# tiny_control.net
KiCad netlist of a schematic drawn in Altium Designer
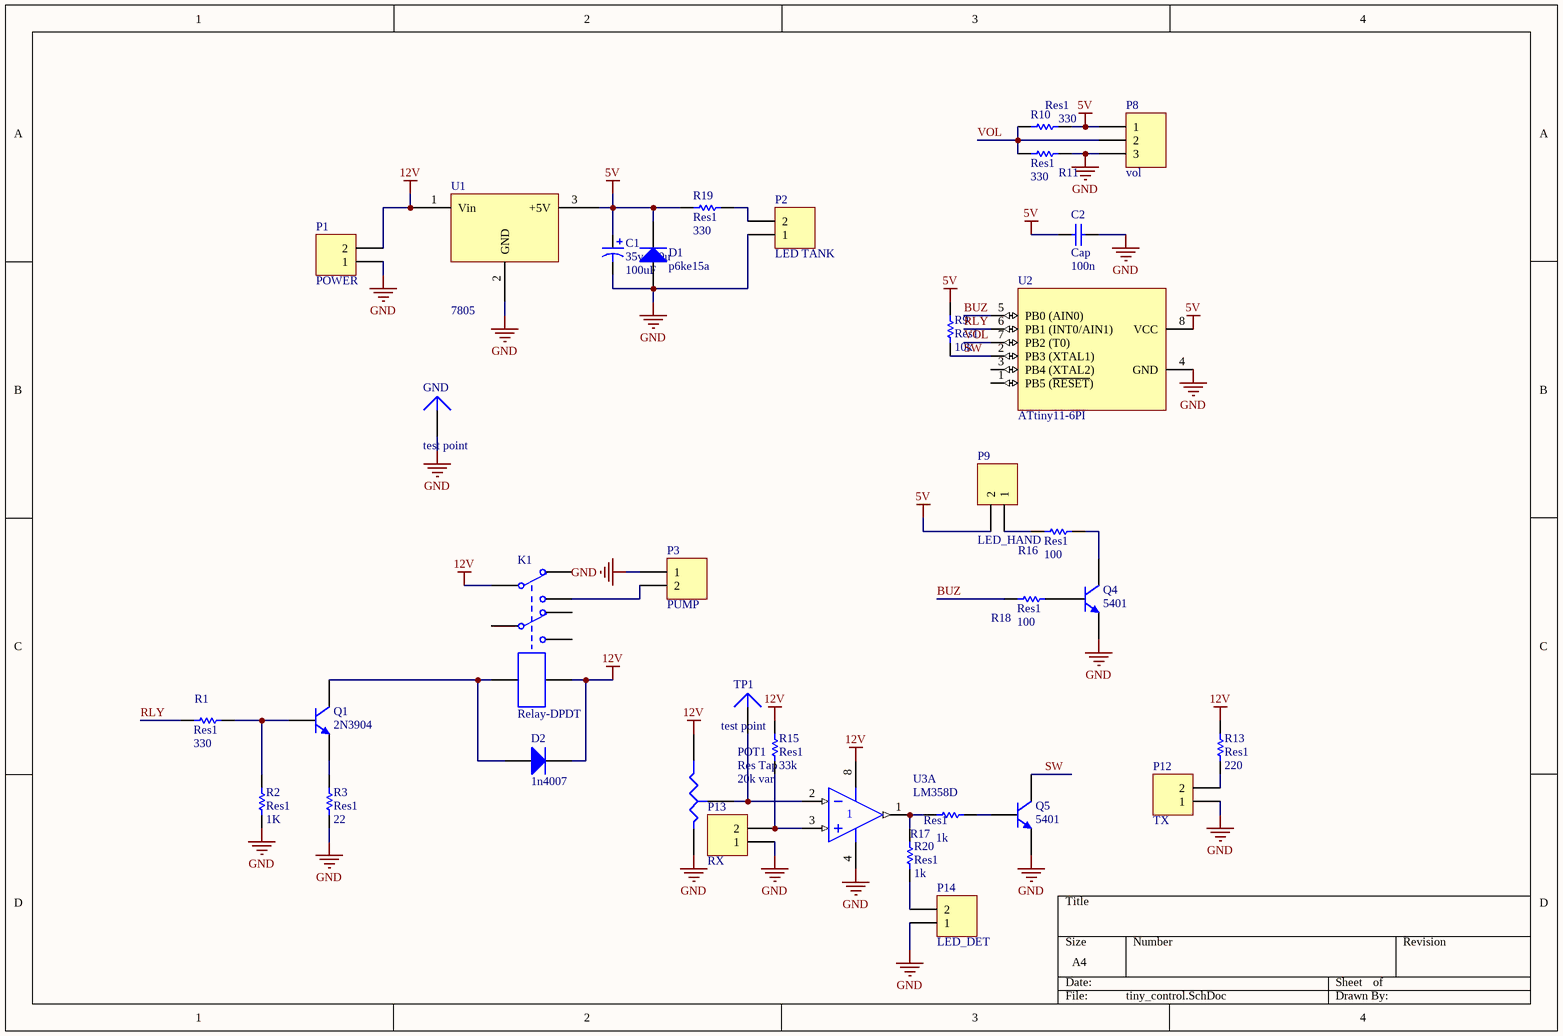
[diagram p0: tiny_control.SchDoc]

(export (version "E")
  (design (tool "Eeschema 10.0.6"))
  (components
    (comp (ref "C1")
      (value "35v 100u")
      (footprint "cap5")
      (description "ELECTROLITE 25V")
      (fields (field (name "ALTIUM_VALUE") "100uF"))
      (libsource (lib "Miscellaneous Devices") (part "Cap Pol1"))
    )
    (comp (ref "C2")
      (value "Cap")
      (footprint "RAD-0.1")
      (description "Capacitor")
      (fields (field (name "ALTIUM_VALUE") "100n") (field (name "PUBLISHER") "Altium Limited"))
      (libsource (lib "Miscellaneous Devices") (part "Cap"))
    )
    (comp (ref "D1")
      (value "p6ke15a")
      (footprint "DIODE-0.4")
      (description "High Conductance Fast Diode")
      (libsource (lib "Miscellaneous Devices") (part "Diode 1N4148"))
    )
    (comp (ref "D2")
      (value "1n4007")
      (footprint "DIO7.1-3.9x1.9")
      (description "High Conductance Fast Diode")
      (libsource (lib "Miscellaneous Devices") (part "Diode 1N4148"))
    )
    (comp (ref "GND")
      (value "test point")
      (footprint "PIN1")
      (description "Plug")
      (fields (field (name "PUBLISHER") "Altium Limited"))
      (libsource (lib "Miscellaneous Connectors") (part "Plug"))
    )
    (comp (ref "K1")
      (value "Relay-DPDT")
      (footprint "My_REL_cochick")
      (description "Dual-Pole Dual-Throw Relay")
      (fields (field (name "PUBLISHER") "Altium Limited"))
      (libsource (lib "Miscellaneous Devices") (part "Relay-DPDT"))
    )
    (comp (ref "P1")
      (value "POWER")
      (footprint "con2_2.54")
      (description "Header, 2-Pin")
      (fields (field (name "PUBLISHER") "Altium Limited"))
      (libsource (lib "Miscellaneous Connectors") (part "Header 2"))
    )
    (comp (ref "P2")
      (value "LED TANK")
      (footprint "con2_2.54")
      (description "Header, 2-Pin")
      (fields (field (name "PUBLISHER") "Altium Limited"))
      (libsource (lib "") (part "Header 2_2"))
    )
    (comp (ref "P3")
      (value "PUMP")
      (footprint "con2_2.54")
      (description "Header, 2-Pin")
      (fields (field (name "PUBLISHER") "Altium Limited"))
      (libsource (lib "") (part "Header 2_1"))
    )
    (comp (ref "P8")
      (value "vol")
      (footprint "con3_2.54")
      (description "Header, 3-Pin")
      (fields (field (name "PUBLISHER") "Altium Limited"))
      (libsource (lib "Miscellaneous Connectors") (part "Header 3"))
    )
    (comp (ref "P9")
      (value "LED_HAND")
      (footprint "con2_2.54")
      (description "Header, 2-Pin")
      (fields (field (name "PUBLISHER") "Altium Limited"))
      (libsource (lib "") (part "Header 2_1"))
    )
    (comp (ref "P12")
      (value "TX")
      (footprint "con2_2.54")
      (description "Header, 2-Pin")
      (fields (field (name "PUBLISHER") "Altium Limited"))
      (libsource (lib "Miscellaneous Connectors") (part "Header 2"))
    )
    (comp (ref "P13")
      (value "RX")
      (footprint "con2_2.54")
      (description "Header, 2-Pin")
      (fields (field (name "PUBLISHER") "Altium Limited"))
      (libsource (lib "Miscellaneous Connectors") (part "Header 2"))
    )
    (comp (ref "P14")
      (value "LED_DET")
      (footprint "con2_2.54")
      (description "Header, 2-Pin")
      (fields (field (name "PUBLISHER") "Altium Limited"))
      (libsource (lib "") (part "Header 2_2"))
    )
    (comp (ref "POT1")
      (value "Res Tap")
      (footprint "VR5")
      (description "Tapped Resistor")
      (fields (field (name "ALTIUM_VALUE") "20k var"))
      (libsource (lib "Miscellaneous Devices") (part "Res Tap"))
    )
    (comp (ref "Q1")
      (value "2N3904")
      (footprint "TO-92C")
      (description "NPN General Purpose Amplifier")
      (fields (field (name "PUBLISHER") "Altium Limited"))
      (libsource (lib "Miscellaneous Devices") (part "2N3904"))
    )
    (comp (ref "Q4")
      (value "5401")
      (footprint "TO-92C")
      (description "Transistor")
      (fields (field (name "PUBLISHER") "Altium Limited"))
      (libsource (lib "Motorola Discrete BJT") (part "P2N2222A"))
    )
    (comp (ref "Q5")
      (value "5401")
      (footprint "TO-92C")
      (description "Transistor")
      (fields (field (name "PUBLISHER") "Altium Limited"))
      (libsource (lib "Motorola Discrete BJT") (part "P2N2222A"))
    )
    (comp (ref "R1")
      (value "Res1")
      (footprint "AXIAL-0.3")
      (description "Resistor")
      (fields (field (name "ALTIUM_VALUE") "330") (field (name "PUBLISHER") "Altium Limited"))
      (libsource (lib "Miscellaneous Devices") (part "Res1"))
    )
    (comp (ref "R2")
      (value "Res1")
      (footprint "AXIAL-0.3")
      (description "Resistor")
      (fields (field (name "ALTIUM_VALUE") "1K") (field (name "PUBLISHER") "Altium Limited"))
      (libsource (lib "Miscellaneous Devices") (part "Res1"))
    )
    (comp (ref "R3")
      (value "Res1")
      (footprint "AXIAL-0.3")
      (description "Resistor")
      (fields (field (name "ALTIUM_VALUE") "22") (field (name "PUBLISHER") "Altium Limited"))
      (libsource (lib "Miscellaneous Devices") (part "Res1"))
    )
    (comp (ref "R9")
      (value "Res1")
      (footprint "AXIAL-0.3")
      (description "Resistor")
      (fields (field (name "ALTIUM_VALUE") "10k") (field (name "PUBLISHER") "Altium Limited"))
      (libsource (lib "Miscellaneous Devices") (part "Res1"))
    )
    (comp (ref "R10")
      (value "Res1")
      (footprint "AXIAL-0.3")
      (description "Resistor")
      (fields (field (name "ALTIUM_VALUE") "330") (field (name "PUBLISHER") "Altium Limited"))
      (libsource (lib "Miscellaneous Devices") (part "Res1"))
    )
    (comp (ref "R11")
      (value "Res1")
      (footprint "AXIAL-0.3")
      (description "Resistor")
      (fields (field (name "ALTIUM_VALUE") "330") (field (name "PUBLISHER") "Altium Limited"))
      (libsource (lib "Miscellaneous Devices") (part "Res1"))
    )
    (comp (ref "R13")
      (value "Res1")
      (footprint "AXIAL-0.3")
      (description "Resistor")
      (fields (field (name "ALTIUM_VALUE") "220") (field (name "PUBLISHER") "Altium Limited"))
      (libsource (lib "Miscellaneous Devices") (part "Res1"))
    )
    (comp (ref "R15")
      (value "Res1")
      (footprint "AXIAL-0.3")
      (description "Resistor")
      (fields (field (name "ALTIUM_VALUE") "33k") (field (name "PUBLISHER") "Altium Limited"))
      (libsource (lib "Miscellaneous Devices") (part "Res1"))
    )
    (comp (ref "R16")
      (value "Res1")
      (footprint "AXIAL-0.3")
      (description "Resistor")
      (fields (field (name "ALTIUM_VALUE") "100") (field (name "PUBLISHER") "Altium Limited"))
      (libsource (lib "Miscellaneous Devices") (part "Res1"))
    )
    (comp (ref "R17")
      (value "Res1")
      (footprint "AXIAL-0.3")
      (description "Resistor")
      (fields (field (name "ALTIUM_VALUE") "1k") (field (name "PUBLISHER") "Altium Limited"))
      (libsource (lib "Miscellaneous Devices") (part "Res1"))
    )
    (comp (ref "R18")
      (value "Res1")
      (footprint "AXIAL-0.3")
      (description "Resistor")
      (fields (field (name "ALTIUM_VALUE") "100") (field (name "PUBLISHER") "Altium Limited"))
      (libsource (lib "Miscellaneous Devices") (part "Res1"))
    )
    (comp (ref "R19")
      (value "Res1")
      (footprint "AXIAL-0.3")
      (description "Resistor")
      (fields (field (name "ALTIUM_VALUE") "330") (field (name "PUBLISHER") "Altium Limited"))
      (libsource (lib "Miscellaneous Devices") (part "Res1"))
    )
    (comp (ref "R20")
      (value "Res1")
      (footprint "AXIAL-0.3")
      (description "Resistor")
      (fields (field (name "ALTIUM_VALUE") "1k") (field (name "PUBLISHER") "Altium Limited"))
      (libsource (lib "Miscellaneous Devices") (part "Res1"))
    )
    (comp (ref "TP1")
      (value "test point")
      (footprint "PIN1")
      (description "Plug")
      (fields (field (name "PUBLISHER") "Altium Limited"))
      (libsource (lib "Miscellaneous Connectors") (part "Plug"))
    )
    (comp (ref "U1")
      (value "7805")
      (footprint "TO-220")
      (description "Regulator")
      (libsource (lib "AHO") (part "7805"))
    )
    (comp (ref "U2")
      (value "ATtiny11-6PI")
      (footprint "SOIC-8")
      (description "AVR 1K Byte of Flash Memory")
      (fields (field (name "PUBLISHER") "Altium Limited"))
      (libsource (lib "AHO") (part "ATtiny11-6PI"))
    )
    (comp (ref "U3")
      (value "LM358D")
      (footprint "SOIC-8")
      (description "Dual Low-Power Operational Amplifier")
      (libsource (lib "Motorola Amplifier Operational Amplifier") (part "LM358D"))
    )
  )
  (nets
    (net (code "1") (name "/BUZ") (class "Default")
      (node (ref "R18") (pin "1") (pinfunction "1_1") (pintype "passive"))
      (node (ref "U2") (pin "5") (pinfunction "PB0_(AIN0)_5") (pintype "bidirectional"))
    )
    (net (code "2") (name "/RLY") (class "Default")
      (node (ref "R1") (pin "1") (pinfunction "1_1") (pintype "passive"))
      (node (ref "U2") (pin "6") (pinfunction "PB1_(INT0/AIN1)_6") (pintype "bidirectional"))
    )
    (net (code "3") (name "/SW") (class "Default")
      (node (ref "Q5") (pin "1") (pinfunction "C_1") (pintype "passive"))
      (node (ref "R9") (pin "2") (pinfunction "2_2") (pintype "passive"))
      (node (ref "U2") (pin "2") (pinfunction "PB3_(XTAL1)_2") (pintype "bidirectional"))
    )
    (net (code "4") (name "/VOL") (class "Default")
      (node (ref "P8") (pin "2") (pinfunction "2_2") (pintype "passive"))
      (node (ref "R10") (pin "2") (pinfunction "2_2") (pintype "passive"))
      (node (ref "R11") (pin "2") (pinfunction "2_2") (pintype "passive"))
      (node (ref "U2") (pin "7") (pinfunction "PB2_(T0)_7") (pintype "bidirectional"))
    )
    (net (code "5") (name "5V") (class "Default")
      (node (ref "C1") (pin "1") (pinfunction "1_1") (pintype "passive"))
      (node (ref "C2") (pin "1") (pinfunction "1_1") (pintype "passive"))
      (node (ref "D1") (pin "2") (pinfunction "K_2") (pintype "passive"))
      (node (ref "P8") (pin "1") (pinfunction "1_1") (pintype "passive"))
      (node (ref "P9") (pin "2") (pinfunction "2_2") (pintype "passive"))
      (node (ref "R10") (pin "1") (pinfunction "1_1") (pintype "passive"))
      (node (ref "R19") (pin "2") (pinfunction "2_2") (pintype "passive"))
      (node (ref "R9") (pin "1") (pinfunction "1_1") (pintype "passive"))
      (node (ref "U1") (pin "3") (pinfunction "+5V_3") (pintype "power_in"))
      (node (ref "U2") (pin "8") (pinfunction "VCC_8") (pintype "power_in"))
    )
    (net (code "6") (name "12V") (class "Default")
      (node (ref "D2") (pin "2") (pinfunction "K_2") (pintype "passive"))
      (node (ref "K1") (pin "1") (pinfunction "1_1") (pintype "passive"))
      (node (ref "K1") (pin "8") (pinfunction "8_8") (pintype "passive"))
      (node (ref "P1") (pin "2") (pinfunction "2_2") (pintype "passive"))
      (node (ref "POT1") (pin "3") (pinfunction "3_3") (pintype "passive"))
      (node (ref "R13") (pin "2") (pinfunction "2_2") (pintype "passive"))
      (node (ref "R15") (pin "2") (pinfunction "2_2") (pintype "passive"))
      (node (ref "U1") (pin "1") (pinfunction "Vin_1") (pintype "power_in"))
      (node (ref "U3") (pin "8") (pinfunction "V+_8") (pintype "power_in"))
    )
    (net (code "7") (name "GND") (class "Default")
      (node (ref "C1") (pin "2") (pinfunction "2_2") (pintype "passive"))
      (node (ref "C2") (pin "2") (pinfunction "2_2") (pintype "passive"))
      (node (ref "D1") (pin "1") (pinfunction "A_1") (pintype "passive"))
      (node (ref "GND") (pin "1") (pinfunction "1_1") (pintype "passive"))
      (node (ref "P1") (pin "1") (pinfunction "1_1") (pintype "passive"))
      (node (ref "P12") (pin "1") (pinfunction "1_1") (pintype "passive"))
      (node (ref "P13") (pin "1") (pinfunction "1_1") (pintype "passive"))
      (node (ref "P14") (pin "1") (pinfunction "1_1") (pintype "passive"))
      (node (ref "P2") (pin "1") (pinfunction "1_1") (pintype "passive"))
      (node (ref "P3") (pin "1") (pinfunction "1_1") (pintype "passive"))
      (node (ref "P8") (pin "3") (pinfunction "3_3") (pintype "passive"))
      (node (ref "POT1") (pin "1") (pinfunction "1_1") (pintype "passive"))
      (node (ref "Q4") (pin "3") (pinfunction "E_3") (pintype "passive"))
      (node (ref "Q5") (pin "3") (pinfunction "E_3") (pintype "passive"))
      (node (ref "R11") (pin "1") (pinfunction "1_1") (pintype "passive"))
      (node (ref "R2") (pin "1") (pinfunction "1_1") (pintype "passive"))
      (node (ref "R3") (pin "1") (pinfunction "1_1") (pintype "passive"))
      (node (ref "U1") (pin "2") (pinfunction "GND_2") (pintype "power_in"))
      (node (ref "U2") (pin "4") (pinfunction "GND_4") (pintype "power_in"))
      (node (ref "U3") (pin "4") (pinfunction "V-_4") (pintype "power_in"))
    )
    (net (code "8") (name "Net-(D2-A)") (class "Default")
      (node (ref "D2") (pin "1") (pinfunction "A_1") (pintype "passive"))
      (node (ref "K1") (pin "7") (pinfunction "7_7") (pintype "passive"))
      (node (ref "Q1") (pin "3") (pinfunction "C_3") (pintype "passive"))
    )
    (net (code "9") (name "Net-(K1-Pad3)") (class "Default")
      (node (ref "K1") (pin "3") (pinfunction "3_3") (pintype "passive"))
      (node (ref "P3") (pin "2") (pinfunction "2_2") (pintype "passive"))
    )
    (net (code "10") (name "Net-(P2-Pad2)") (class "Default")
      (node (ref "P2") (pin "2") (pinfunction "2_2") (pintype "passive"))
      (node (ref "R19") (pin "1") (pinfunction "1_1") (pintype "passive"))
    )
    (net (code "11") (name "Net-(P9-Pad1)") (class "Default")
      (node (ref "P9") (pin "1") (pinfunction "1_1") (pintype "passive"))
      (node (ref "R16") (pin "1") (pinfunction "1_1") (pintype "passive"))
    )
    (net (code "12") (name "Net-(P12-Pad2)") (class "Default")
      (node (ref "P12") (pin "2") (pinfunction "2_2") (pintype "passive"))
      (node (ref "R13") (pin "1") (pinfunction "1_1") (pintype "passive"))
    )
    (net (code "13") (name "Net-(P14-Pad2)") (class "Default")
      (node (ref "P14") (pin "2") (pinfunction "2_2") (pintype "passive"))
      (node (ref "R20") (pin "1") (pinfunction "1_1") (pintype "passive"))
    )
    (net (code "14") (name "Net-(Q1-B)") (class "Default")
      (node (ref "Q1") (pin "2") (pinfunction "B_2") (pintype "passive"))
      (node (ref "R1") (pin "2") (pinfunction "2_2") (pintype "passive"))
      (node (ref "R2") (pin "2") (pinfunction "2_2") (pintype "passive"))
    )
    (net (code "15") (name "Net-(Q1-E)") (class "Default")
      (node (ref "Q1") (pin "1") (pinfunction "E_1") (pintype "passive"))
      (node (ref "R3") (pin "2") (pinfunction "2_2") (pintype "passive"))
    )
    (net (code "16") (name "Net-(Q4-B)") (class "Default")
      (node (ref "Q4") (pin "2") (pinfunction "B_2") (pintype "passive"))
      (node (ref "R18") (pin "2") (pinfunction "2_2") (pintype "passive"))
    )
    (net (code "17") (name "Net-(Q4-C)") (class "Default")
      (node (ref "Q4") (pin "1") (pinfunction "C_1") (pintype "passive"))
      (node (ref "R16") (pin "2") (pinfunction "2_2") (pintype "passive"))
    )
    (net (code "18") (name "Net-(Q5-B)") (class "Default")
      (node (ref "Q5") (pin "2") (pinfunction "B_2") (pintype "passive"))
      (node (ref "R17") (pin "2") (pinfunction "2_2") (pintype "passive"))
    )
    (net (code "19") (name "Net-(U3A-IN+)") (class "Default")
      (node (ref "P13") (pin "2") (pinfunction "2_2") (pintype "passive"))
      (node (ref "R15") (pin "1") (pinfunction "1_1") (pintype "passive"))
      (node (ref "U3") (pin "3") (pinfunction "IN+_3") (pintype "input"))
    )
    (net (code "20") (name "Net-(U3A-IN-)") (class "Default")
      (node (ref "POT1") (pin "2") (pinfunction "2_2") (pintype "passive"))
      (node (ref "TP1") (pin "1") (pinfunction "1_1") (pintype "passive"))
      (node (ref "U3") (pin "2") (pinfunction "IN-_2") (pintype "input"))
    )
    (net (code "21") (name "Net-(U3A-OUT)") (class "Default")
      (node (ref "R17") (pin "1") (pinfunction "1_1") (pintype "passive"))
      (node (ref "R20") (pin "2") (pinfunction "2_2") (pintype "passive"))
      (node (ref "U3") (pin "1") (pinfunction "OUT_1") (pintype "output"))
    )
    (net (code "22") (name "unconnected-(K1-Pad2)") (class "Default")
      (node (ref "K1") (pin "2") (pinfunction "2_2") (pintype "passive"))
    )
    (net (code "23") (name "unconnected-(K1-Pad4)") (class "Default")
      (node (ref "K1") (pin "4") (pinfunction "4_4") (pintype "passive"))
    )
    (net (code "24") (name "unconnected-(K1-Pad5)") (class "Default")
      (node (ref "K1") (pin "5") (pinfunction "5_5") (pintype "passive"))
    )
    (net (code "25") (name "unconnected-(K1-Pad6)") (class "Default")
      (node (ref "K1") (pin "6") (pinfunction "6_6") (pintype "passive"))
    )
    (net (code "26") (name "unconnected-(U2-PB4_(XTAL2)-Pad3)") (class "Default")
      (node (ref "U2") (pin "3") (pinfunction "PB4_(XTAL2)_3") (pintype "bidirectional"))
    )
    (net (code "27") (name "unconnected-(U2-PB5_(~{RESET})-Pad1)") (class "Default")
      (node (ref "U2") (pin "1") (pinfunction "PB5_(~{RESET})_1") (pintype "bidirectional"))
    )
  )
)
